# arduino_barebone.net
KiCad netlist of a schematic drawn in EAGLE
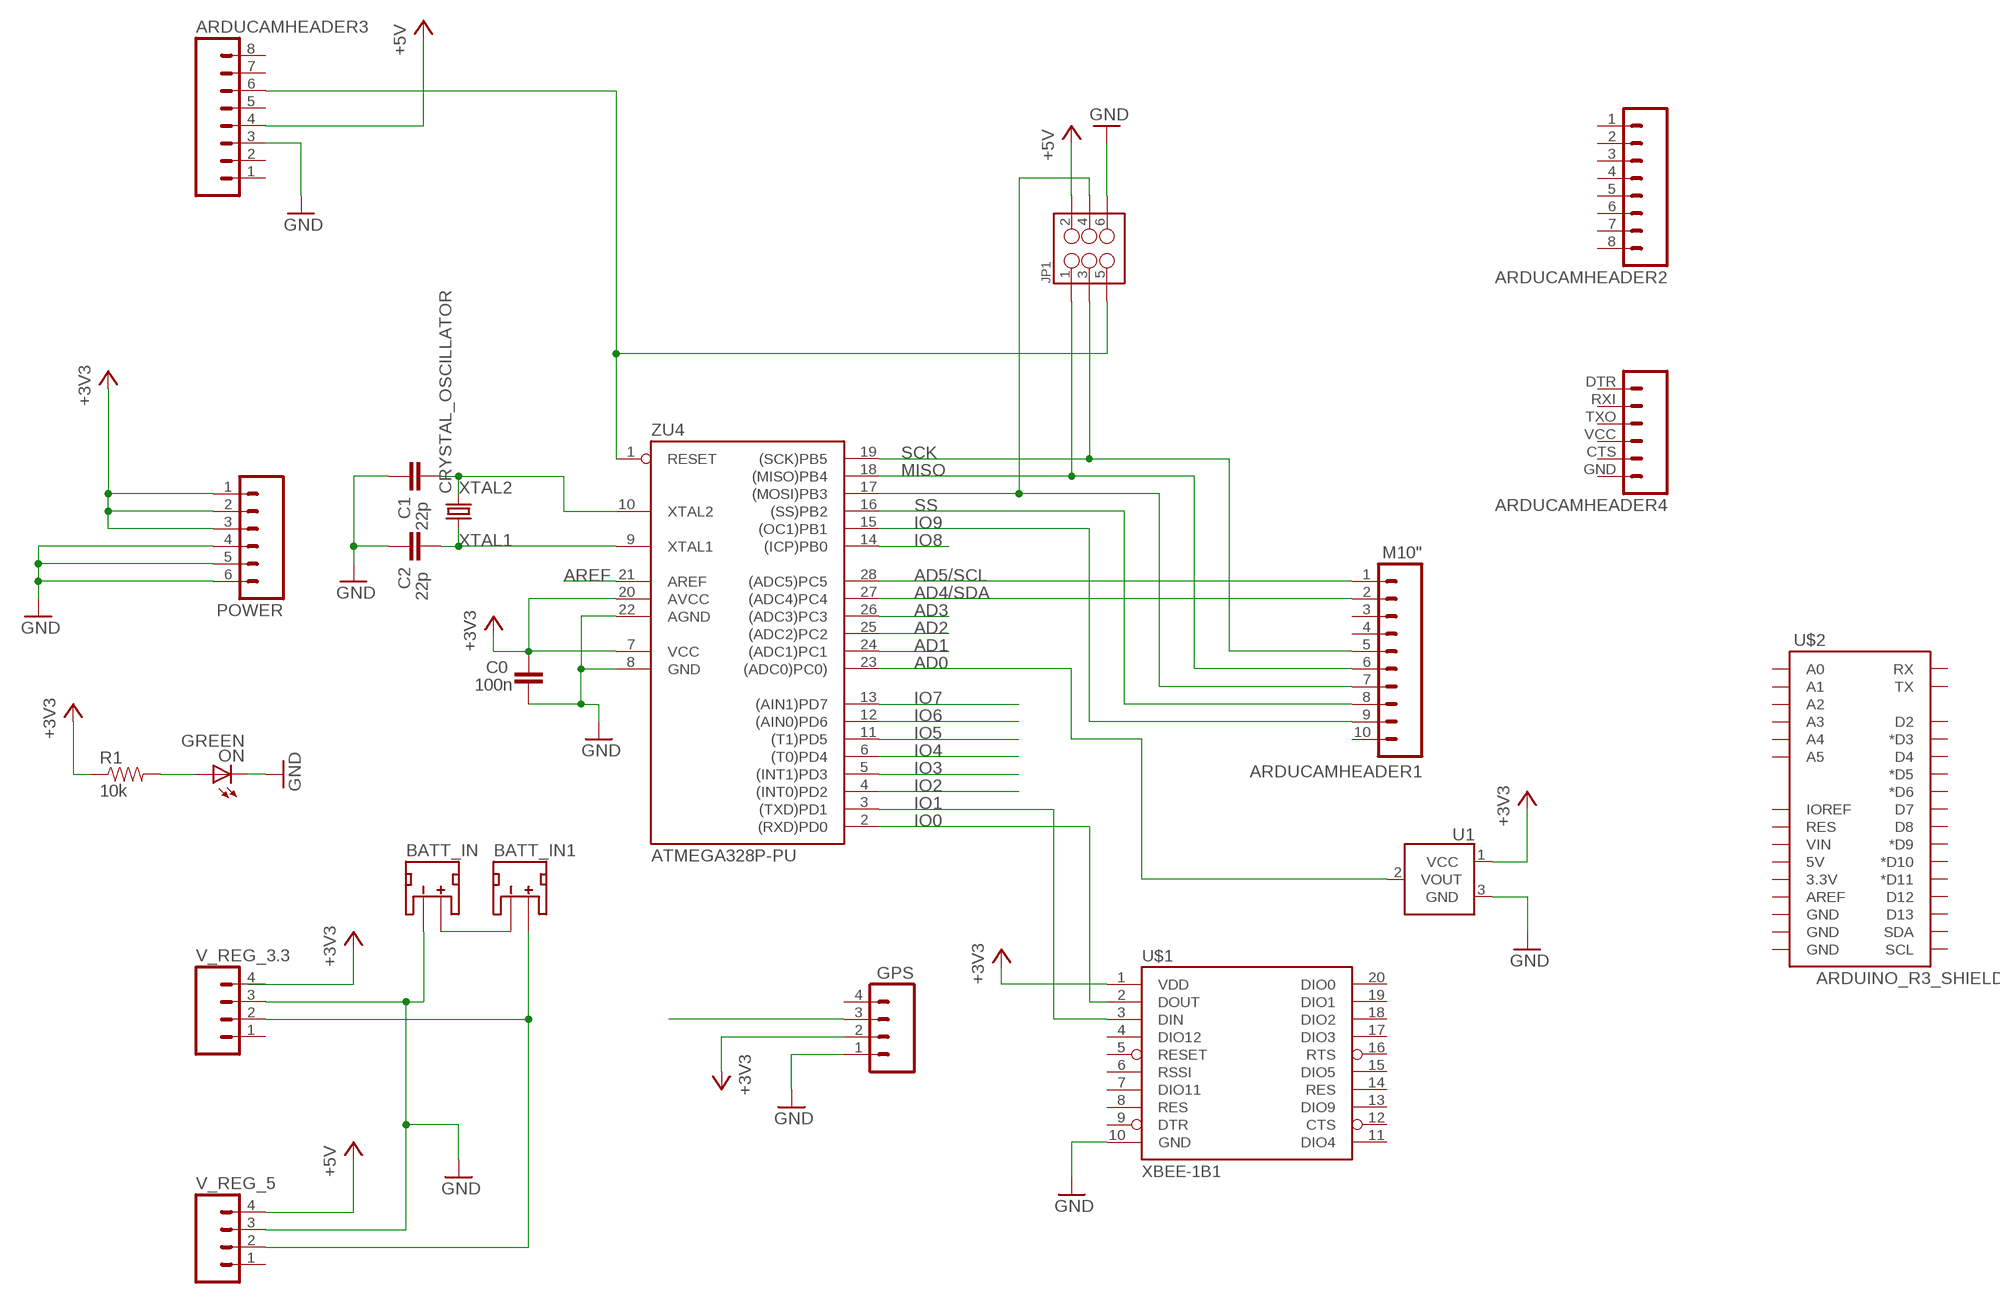
[diagram p0: schematic, sheet 1]

(export (version "E")
  (design (tool "Eeschema 10.0.6"))
  (components
    (comp (ref "ARDUCAMHEADER1")
      (value "M10\"")
      (footprint "eagle-import:1X10")
      (libsource (lib "eagle-import") (part "M10{dblquote}"))
    )
    (comp (ref "ARDUCAMHEADER2")
      (value "M081X08")
      (footprint "eagle-import:1X08")
      (libsource (lib "eagle-import") (part "M081X08"))
    )
    (comp (ref "ARDUCAMHEADER3")
      (value "M081X08")
      (footprint "eagle-import:1X08")
      (libsource (lib "eagle-import") (part "M081X08"))
    )
    (comp (ref "ARDUCAMHEADER4")
      (value "M06SIP")
      (footprint "eagle-import:1X06")
      (libsource (lib "eagle-import") (part "M06SIP"))
    )
    (comp (ref "BATT_IN")
      (value "JST_2MM_MALE")
      (footprint "eagle-import:JST-2-SMD")
      (libsource (lib "eagle-import") (part "JST_2MM_MALE"))
    )
    (comp (ref "BATT_IN1")
      (value "JST_2MM_MALE")
      (footprint "eagle-import:JST-2-SMD")
      (libsource (lib "eagle-import") (part "JST_2MM_MALE"))
    )
    (comp (ref "C0")
      (value "100n")
      (footprint "eagle-import:C0603-ROUND")
      (libsource (lib "eagle-import") (part "C-EU0603-RND"))
    )
    (comp (ref "C1")
      (value "22p")
      (footprint "eagle-import:C0603-ROUND")
      (libsource (lib "eagle-import") (part "C-EU0603-RND"))
    )
    (comp (ref "C2")
      (value "22p")
      (footprint "eagle-import:C0603-ROUND")
      (libsource (lib "eagle-import") (part "C-EU0603-RND"))
    )
    (comp (ref "CRYSTAL_OSCILLATOR")
      (value "CRYSTALHC49US")
      (footprint "eagle-import:HC49US")
      (libsource (lib "eagle-import") (part "CRYSTALHC49US"))
    )
    (comp (ref "GPS")
      (value "M04PTH")
      (footprint "eagle-import:1X04")
      (libsource (lib "eagle-import") (part "M04PTH"))
    )
    (comp (ref "JP1")
      (value "M03X2POGO_PINS")
      (footprint "eagle-import:2X3_POGO")
      (libsource (lib "eagle-import") (part "M03X2POGO_PINS"))
    )
    (comp (ref "ON")
      (value "GREEN")
      (footprint "eagle-import:CHIP-LED0805")
      (libsource (lib "eagle-import") (part "LEDCHIP-LED0805"))
    )
    (comp (ref "POWER")
      (value "M06LONGPADS")
      (footprint "eagle-import:1X06_LONGPADS")
      (libsource (lib "eagle-import") (part "M06LONGPADS"))
    )
    (comp (ref "R1")
      (value "10k")
      (footprint "eagle-import:0805")
      (libsource (lib "eagle-import") (part "RESISTOR"))
    )
    (comp (ref "U$1")
      (value "XBEE-1B1")
      (footprint "eagle-import:XBEE-1")
      (libsource (lib "eagle-import") (part "XBEE-1B1"))
    )
    (comp (ref "U$2")
      (value "ARDUINO_R3_SHIELD")
      (footprint "eagle-import:UNO_R3_SHIELD")
      (libsource (lib "eagle-import") (part "ARDUINO_R3_SHIELD"))
    )
    (comp (ref "U1")
      (value "TMP36GT9")
      (footprint "eagle-import:TO-92")
      (libsource (lib "eagle-import") (part "TMP36GT9"))
    )
    (comp (ref "V_REG_3.3")
      (value "M04PTH")
      (footprint "eagle-import:1X04")
      (libsource (lib "eagle-import") (part "M04PTH"))
    )
    (comp (ref "V_REG_5")
      (value "M04PTH")
      (footprint "eagle-import:1X04")
      (libsource (lib "eagle-import") (part "M04PTH"))
    )
    (comp (ref "ZU4")
      (value "ATMEGA328P-PU")
      (footprint "eagle-import:DIL28-3")
      (libsource (lib "eagle-import") (part "ATMEGA328P-PU"))
    )
  )
  (nets
    (net (code "1") (name "+3V3") (class "Default")
      (node (ref "C0") (pin "2") (pinfunction "2_2") (pintype "passive"))
      (node (ref "GPS") (pin "2") (pinfunction "2_2") (pintype "passive"))
      (node (ref "POWER") (pin "1") (pinfunction "1_1") (pintype "passive"))
      (node (ref "POWER") (pin "2") (pinfunction "2_2") (pintype "passive"))
      (node (ref "POWER") (pin "3") (pinfunction "3_3") (pintype "passive"))
      (node (ref "R1") (pin "1") (pinfunction "1_1") (pintype "passive"))
      (node (ref "U$1") (pin "1") (pinfunction "VDD_1") (pintype "power_in"))
      (node (ref "U1") (pin "1") (pinfunction "VCC_1") (pintype "bidirectional"))
      (node (ref "V_REG_3.3") (pin "4") (pinfunction "4_4") (pintype "passive"))
      (node (ref "ZU4") (pin "20") (pinfunction "AVCC_20") (pintype "power_in"))
      (node (ref "ZU4") (pin "7") (pinfunction "VCC_7") (pintype "power_in"))
    )
    (net (code "2") (name "+5V") (class "Default")
      (node (ref "ARDUCAMHEADER3") (pin "4") (pinfunction "4_4") (pintype "passive"))
      (node (ref "JP1") (pin "P$2") (pinfunction "2_P$2") (pintype "bidirectional"))
      (node (ref "V_REG_5") (pin "4") (pinfunction "4_4") (pintype "passive"))
    )
    (net (code "3") (name "/AD0") (class "Default")
      (node (ref "U1") (pin "2") (pinfunction "VOUT_2") (pintype "bidirectional"))
      (node (ref "ZU4") (pin "23") (pinfunction "(ADC0)PC0)_23") (pintype "bidirectional"))
    )
    (net (code "4") (name "/AD1") (class "Default")
      (node (ref "ZU4") (pin "24") (pinfunction "(ADC1)PC1_24") (pintype "bidirectional"))
    )
    (net (code "5") (name "/AD2") (class "Default")
      (node (ref "ZU4") (pin "25") (pinfunction "(ADC2)PC2_25") (pintype "bidirectional"))
    )
    (net (code "6") (name "/AD3") (class "Default")
      (node (ref "ZU4") (pin "26") (pinfunction "(ADC3)PC3_26") (pintype "bidirectional"))
    )
    (net (code "7") (name "/AD4{slash}SDA") (class "Default")
      (node (ref "ARDUCAMHEADER1") (pin "2") (pinfunction "2_2") (pintype "passive"))
      (node (ref "ZU4") (pin "27") (pinfunction "(ADC4)PC4_27") (pintype "bidirectional"))
    )
    (net (code "8") (name "/AD5{slash}SCL") (class "Default")
      (node (ref "ARDUCAMHEADER1") (pin "1") (pinfunction "1_1") (pintype "passive"))
      (node (ref "ZU4") (pin "28") (pinfunction "(ADC5)PC5_28") (pintype "bidirectional"))
    )
    (net (code "9") (name "/AREF") (class "Default")
      (node (ref "ZU4") (pin "21") (pinfunction "AREF_21") (pintype "passive"))
    )
    (net (code "10") (name "/IO0") (class "Default")
      (node (ref "U$1") (pin "2") (pinfunction "DOUT_2") (pintype "output"))
      (node (ref "ZU4") (pin "2") (pinfunction "(RXD)PD0_2") (pintype "bidirectional"))
    )
    (net (code "11") (name "/IO1") (class "Default")
      (node (ref "U$1") (pin "3") (pinfunction "DIN_3") (pintype "input"))
      (node (ref "ZU4") (pin "3") (pinfunction "(TXD)PD1_3") (pintype "bidirectional"))
    )
    (net (code "12") (name "/IO2") (class "Default")
      (node (ref "ZU4") (pin "4") (pinfunction "(INT0)PD2_4") (pintype "bidirectional"))
    )
    (net (code "13") (name "/IO3") (class "Default")
      (node (ref "ZU4") (pin "5") (pinfunction "(INT1)PD3_5") (pintype "bidirectional"))
    )
    (net (code "14") (name "/IO4") (class "Default")
      (node (ref "ZU4") (pin "6") (pinfunction "(T0)PD4_6") (pintype "bidirectional"))
    )
    (net (code "15") (name "/IO5") (class "Default")
      (node (ref "ZU4") (pin "11") (pinfunction "(T1)PD5_11") (pintype "bidirectional"))
    )
    (net (code "16") (name "/IO6") (class "Default")
      (node (ref "ZU4") (pin "12") (pinfunction "(AIN0)PD6_12") (pintype "bidirectional"))
    )
    (net (code "17") (name "/IO7") (class "Default")
      (node (ref "ZU4") (pin "13") (pinfunction "(AIN1)PD7_13") (pintype "bidirectional"))
    )
    (net (code "18") (name "/IO8") (class "Default")
      (node (ref "ZU4") (pin "14") (pinfunction "(ICP)PB0_14") (pintype "bidirectional"))
    )
    (net (code "19") (name "/IO9") (class "Default")
      (node (ref "ARDUCAMHEADER1") (pin "9") (pinfunction "9_9") (pintype "passive"))
      (node (ref "ZU4") (pin "15") (pinfunction "(OC1)PB1_15") (pintype "bidirectional"))
    )
    (net (code "20") (name "/MISO") (class "Default")
      (node (ref "ARDUCAMHEADER1") (pin "6") (pinfunction "6_6") (pintype "passive"))
      (node (ref "JP1") (pin "P$1") (pinfunction "1_P$1") (pintype "bidirectional"))
      (node (ref "ZU4") (pin "18") (pinfunction "(MISO)PB4_18") (pintype "bidirectional"))
    )
    (net (code "21") (name "/SCK") (class "Default")
      (node (ref "ARDUCAMHEADER1") (pin "5") (pinfunction "5_5") (pintype "passive"))
      (node (ref "JP1") (pin "P$3") (pinfunction "3_P$3") (pintype "bidirectional"))
      (node (ref "ZU4") (pin "19") (pinfunction "(SCK)PB5_19") (pintype "bidirectional"))
    )
    (net (code "22") (name "/SS") (class "Default")
      (node (ref "ARDUCAMHEADER1") (pin "8") (pinfunction "8_8") (pintype "passive"))
      (node (ref "ZU4") (pin "16") (pinfunction "(SS)PB2_16") (pintype "bidirectional"))
    )
    (net (code "23") (name "/XTAL1") (class "Default")
      (node (ref "C2") (pin "1") (pinfunction "1_1") (pintype "passive"))
      (node (ref "CRYSTAL_OSCILLATOR") (pin "1") (pinfunction "1_1") (pintype "passive"))
      (node (ref "ZU4") (pin "9") (pinfunction "XTAL1_9") (pintype "bidirectional"))
    )
    (net (code "24") (name "/XTAL2") (class "Default")
      (node (ref "C1") (pin "1") (pinfunction "1_1") (pintype "passive"))
      (node (ref "CRYSTAL_OSCILLATOR") (pin "2") (pinfunction "2_2") (pintype "passive"))
      (node (ref "ZU4") (pin "10") (pinfunction "XTAL2_10") (pintype "bidirectional"))
    )
    (net (code "25") (name "GND") (class "Default")
      (node (ref "ARDUCAMHEADER3") (pin "3") (pinfunction "3_3") (pintype "passive"))
      (node (ref "BATT_IN") (pin "1") (pinfunction "-_1") (pintype "bidirectional"))
      (node (ref "C0") (pin "1") (pinfunction "1_1") (pintype "passive"))
      (node (ref "C1") (pin "2") (pinfunction "2_2") (pintype "passive"))
      (node (ref "C2") (pin "2") (pinfunction "2_2") (pintype "passive"))
      (node (ref "GPS") (pin "1") (pinfunction "1_1") (pintype "passive"))
      (node (ref "JP1") (pin "P$6") (pinfunction "6_P$6") (pintype "bidirectional"))
      (node (ref "ON") (pin "C") (pinfunction "C_C") (pintype "passive"))
      (node (ref "POWER") (pin "4") (pinfunction "4_4") (pintype "passive"))
      (node (ref "POWER") (pin "5") (pinfunction "5_5") (pintype "passive"))
      (node (ref "POWER") (pin "6") (pinfunction "6_6") (pintype "passive"))
      (node (ref "U$1") (pin "10") (pinfunction "GND_10") (pintype "power_in"))
      (node (ref "U1") (pin "3") (pinfunction "GND_3") (pintype "bidirectional"))
      (node (ref "V_REG_3.3") (pin "3") (pinfunction "3_3") (pintype "passive"))
      (node (ref "V_REG_5") (pin "3") (pinfunction "3_3") (pintype "passive"))
      (node (ref "ZU4") (pin "22") (pinfunction "AGND_22") (pintype "power_in"))
      (node (ref "ZU4") (pin "8") (pinfunction "GND_8") (pintype "power_in"))
    )
    (net (code "26") (name "Net-(BATT_IN-+)") (class "Default")
      (node (ref "BATT_IN") (pin "2") (pinfunction "+_2") (pintype "bidirectional"))
      (node (ref "BATT_IN1") (pin "1") (pinfunction "-_1") (pintype "bidirectional"))
    )
    (net (code "27") (name "Net-(BATT_IN1-+)") (class "Default")
      (node (ref "BATT_IN1") (pin "2") (pinfunction "+_2") (pintype "bidirectional"))
      (node (ref "V_REG_3.3") (pin "2") (pinfunction "2_2") (pintype "passive"))
      (node (ref "V_REG_5") (pin "2") (pinfunction "2_2") (pintype "passive"))
    )
    (net (code "28") (name "Net-(JP1-4)") (class "Default")
      (node (ref "ARDUCAMHEADER1") (pin "7") (pinfunction "7_7") (pintype "passive"))
      (node (ref "JP1") (pin "P$4") (pinfunction "4_P$4") (pintype "bidirectional"))
      (node (ref "ZU4") (pin "17") (pinfunction "(MOSI)PB3_17") (pintype "bidirectional"))
    )
    (net (code "29") (name "Net-(JP1-5)") (class "Default")
      (node (ref "ARDUCAMHEADER3") (pin "6") (pinfunction "6_6") (pintype "passive"))
      (node (ref "JP1") (pin "P$5") (pinfunction "5_P$5") (pintype "bidirectional"))
      (node (ref "ZU4") (pin "1") (pinfunction "RESET_1") (pintype "input"))
    )
    (net (code "30") (name "Net-(ON-PadA)") (class "Default")
      (node (ref "ON") (pin "A") (pinfunction "A_A") (pintype "passive"))
      (node (ref "R1") (pin "2") (pinfunction "2_2") (pintype "passive"))
    )
    (net (code "31") (name "unconnected-(ARDUCAMHEADER1-Pad3)") (class "Default")
      (node (ref "ARDUCAMHEADER1") (pin "3") (pinfunction "3_3") (pintype "passive"))
    )
    (net (code "32") (name "unconnected-(ARDUCAMHEADER1-Pad4)") (class "Default")
      (node (ref "ARDUCAMHEADER1") (pin "4") (pinfunction "4_4") (pintype "passive"))
    )
    (net (code "33") (name "unconnected-(ARDUCAMHEADER1-Pad10)") (class "Default")
      (node (ref "ARDUCAMHEADER1") (pin "10") (pinfunction "10_10") (pintype "passive"))
    )
    (net (code "34") (name "unconnected-(ARDUCAMHEADER2-Pad1)") (class "Default")
      (node (ref "ARDUCAMHEADER2") (pin "1") (pinfunction "1_1") (pintype "passive"))
    )
    (net (code "35") (name "unconnected-(ARDUCAMHEADER2-Pad2)") (class "Default")
      (node (ref "ARDUCAMHEADER2") (pin "2") (pinfunction "2_2") (pintype "passive"))
    )
    (net (code "36") (name "unconnected-(ARDUCAMHEADER2-Pad3)") (class "Default")
      (node (ref "ARDUCAMHEADER2") (pin "3") (pinfunction "3_3") (pintype "passive"))
    )
    (net (code "37") (name "unconnected-(ARDUCAMHEADER2-Pad4)") (class "Default")
      (node (ref "ARDUCAMHEADER2") (pin "4") (pinfunction "4_4") (pintype "passive"))
    )
    (net (code "38") (name "unconnected-(ARDUCAMHEADER2-Pad5)") (class "Default")
      (node (ref "ARDUCAMHEADER2") (pin "5") (pinfunction "5_5") (pintype "passive"))
    )
    (net (code "39") (name "unconnected-(ARDUCAMHEADER2-Pad6)") (class "Default")
      (node (ref "ARDUCAMHEADER2") (pin "6") (pinfunction "6_6") (pintype "passive"))
    )
    (net (code "40") (name "unconnected-(ARDUCAMHEADER2-Pad7)") (class "Default")
      (node (ref "ARDUCAMHEADER2") (pin "7") (pinfunction "7_7") (pintype "passive"))
    )
    (net (code "41") (name "unconnected-(ARDUCAMHEADER2-Pad8)") (class "Default")
      (node (ref "ARDUCAMHEADER2") (pin "8") (pinfunction "8_8") (pintype "passive"))
    )
    (net (code "42") (name "unconnected-(ARDUCAMHEADER3-Pad1)") (class "Default")
      (node (ref "ARDUCAMHEADER3") (pin "1") (pinfunction "1_1") (pintype "passive"))
    )
    (net (code "43") (name "unconnected-(ARDUCAMHEADER3-Pad2)") (class "Default")
      (node (ref "ARDUCAMHEADER3") (pin "2") (pinfunction "2_2") (pintype "passive"))
    )
    (net (code "44") (name "unconnected-(ARDUCAMHEADER3-Pad5)") (class "Default")
      (node (ref "ARDUCAMHEADER3") (pin "5") (pinfunction "5_5") (pintype "passive"))
    )
    (net (code "45") (name "unconnected-(ARDUCAMHEADER3-Pad7)") (class "Default")
      (node (ref "ARDUCAMHEADER3") (pin "7") (pinfunction "7_7") (pintype "passive"))
    )
    (net (code "46") (name "unconnected-(ARDUCAMHEADER3-Pad8)") (class "Default")
      (node (ref "ARDUCAMHEADER3") (pin "8") (pinfunction "8_8") (pintype "passive"))
    )
    (net (code "47") (name "unconnected-(ARDUCAMHEADER4-1-PadDTR)") (class "Default")
      (node (ref "ARDUCAMHEADER4") (pin "DTR") (pinfunction "1_DTR") (pintype "passive"))
    )
    (net (code "48") (name "unconnected-(ARDUCAMHEADER4-2-PadRXI)") (class "Default")
      (node (ref "ARDUCAMHEADER4") (pin "RXI") (pinfunction "2_RXI") (pintype "passive"))
    )
    (net (code "49") (name "unconnected-(ARDUCAMHEADER4-3-PadTXO)") (class "Default")
      (node (ref "ARDUCAMHEADER4") (pin "TXO") (pinfunction "3_TXO") (pintype "passive"))
    )
    (net (code "50") (name "unconnected-(ARDUCAMHEADER4-4-PadVCC)") (class "Default")
      (node (ref "ARDUCAMHEADER4") (pin "VCC") (pinfunction "4_VCC") (pintype "passive"))
    )
    (net (code "51") (name "unconnected-(ARDUCAMHEADER4-5-PadCTS)") (class "Default")
      (node (ref "ARDUCAMHEADER4") (pin "CTS") (pinfunction "5_CTS") (pintype "passive"))
    )
    (net (code "52") (name "unconnected-(ARDUCAMHEADER4-6-PadGND)") (class "Default")
      (node (ref "ARDUCAMHEADER4") (pin "GND") (pinfunction "6_GND") (pintype "passive"))
    )
    (net (code "53") (name "unconnected-(BATT_IN-PAD1-PadNC1)") (class "Default")
      (node (ref "BATT_IN") (pin "NC1") (pinfunction "PAD1_NC1") (pintype "bidirectional"))
    )
    (net (code "54") (name "unconnected-(BATT_IN-PAD2-PadNC2)") (class "Default")
      (node (ref "BATT_IN") (pin "NC2") (pinfunction "PAD2_NC2") (pintype "bidirectional"))
    )
    (net (code "55") (name "unconnected-(BATT_IN1-PAD1-PadNC1)") (class "Default")
      (node (ref "BATT_IN1") (pin "NC1") (pinfunction "PAD1_NC1") (pintype "bidirectional"))
    )
    (net (code "56") (name "unconnected-(BATT_IN1-PAD2-PadNC2)") (class "Default")
      (node (ref "BATT_IN1") (pin "NC2") (pinfunction "PAD2_NC2") (pintype "bidirectional"))
    )
    (net (code "57") (name "unconnected-(GPS-Pad3)") (class "Default")
      (node (ref "GPS") (pin "3") (pinfunction "3_3") (pintype "passive"))
    )
    (net (code "58") (name "unconnected-(GPS-Pad4)") (class "Default")
      (node (ref "GPS") (pin "4") (pinfunction "4_4") (pintype "passive"))
    )
    (net (code "59") (name "unconnected-(U$1-CTS-Pad12)") (class "Default")
      (node (ref "U$1") (pin "12") (pinfunction "CTS_12") (pintype "output"))
    )
    (net (code "60") (name "unconnected-(U$1-DIO0-Pad20)") (class "Default")
      (node (ref "U$1") (pin "20") (pinfunction "DIO0_20") (pintype "bidirectional"))
    )
    (net (code "61") (name "unconnected-(U$1-DIO1-Pad19)") (class "Default")
      (node (ref "U$1") (pin "19") (pinfunction "DIO1_19") (pintype "bidirectional"))
    )
    (net (code "62") (name "unconnected-(U$1-DIO2-Pad18)") (class "Default")
      (node (ref "U$1") (pin "18") (pinfunction "DIO2_18") (pintype "bidirectional"))
    )
    (net (code "63") (name "unconnected-(U$1-DIO3-Pad17)") (class "Default")
      (node (ref "U$1") (pin "17") (pinfunction "DIO3_17") (pintype "bidirectional"))
    )
    (net (code "64") (name "unconnected-(U$1-DIO4-Pad11)") (class "Default")
      (node (ref "U$1") (pin "11") (pinfunction "DIO4_11") (pintype "bidirectional"))
    )
    (net (code "65") (name "unconnected-(U$1-DIO5-Pad15)") (class "Default")
      (node (ref "U$1") (pin "15") (pinfunction "DIO5_15") (pintype "bidirectional"))
    )
    (net (code "66") (name "unconnected-(U$1-DIO9-Pad13)") (class "Default")
      (node (ref "U$1") (pin "13") (pinfunction "DIO9_13") (pintype "bidirectional"))
    )
    (net (code "67") (name "unconnected-(U$1-DIO11-Pad7)") (class "Default")
      (node (ref "U$1") (pin "7") (pinfunction "DIO11_7") (pintype "bidirectional"))
    )
    (net (code "68") (name "unconnected-(U$1-DIO12-Pad4)") (class "Default")
      (node (ref "U$1") (pin "4") (pinfunction "DIO12_4") (pintype "bidirectional"))
    )
    (net (code "69") (name "unconnected-(U$1-DTR-Pad9)") (class "Default")
      (node (ref "U$1") (pin "9") (pinfunction "DTR_9") (pintype "bidirectional"))
    )
    (net (code "70") (name "unconnected-(U$1-RES-Pad8)") (class "Default")
      (node (ref "U$1") (pin "8") (pinfunction "RES_8") (pintype "bidirectional"))
    )
    (net (code "71") (name "unconnected-(U$1-RES-Pad14)") (class "Default")
      (node (ref "U$1") (pin "14") (pinfunction "RES_14") (pintype "bidirectional"))
    )
    (net (code "72") (name "unconnected-(U$1-RESET-Pad5)") (class "Default")
      (node (ref "U$1") (pin "5") (pinfunction "RESET_5") (pintype "input"))
    )
    (net (code "73") (name "unconnected-(U$1-RSSI-Pad6)") (class "Default")
      (node (ref "U$1") (pin "6") (pinfunction "RSSI_6") (pintype "bidirectional"))
    )
    (net (code "74") (name "unconnected-(U$1-RTS-Pad16)") (class "Default")
      (node (ref "U$1") (pin "16") (pinfunction "RTS_16") (pintype "input"))
    )
    (net (code "75") (name "unconnected-(U$2-*D3-PadD3)") (class "Default")
      (node (ref "U$2") (pin "D3") (pinfunction "*D3_D3") (pintype "bidirectional"))
    )
    (net (code "76") (name "unconnected-(U$2-*D5-PadD5)") (class "Default")
      (node (ref "U$2") (pin "D5") (pinfunction "*D5_D5") (pintype "bidirectional"))
    )
    (net (code "77") (name "unconnected-(U$2-*D6-PadD6)") (class "Default")
      (node (ref "U$2") (pin "D6") (pinfunction "*D6_D6") (pintype "bidirectional"))
    )
    (net (code "78") (name "unconnected-(U$2-*D9-PadD9)") (class "Default")
      (node (ref "U$2") (pin "D9") (pinfunction "*D9_D9") (pintype "bidirectional"))
    )
    (net (code "79") (name "unconnected-(U$2-*D10-PadD10)") (class "Default")
      (node (ref "U$2") (pin "D10") (pinfunction "*D10_D10") (pintype "bidirectional"))
    )
    (net (code "80") (name "unconnected-(U$2-*D11-PadD11)") (class "Default")
      (node (ref "U$2") (pin "D11") (pinfunction "*D11_D11") (pintype "bidirectional"))
    )
    (net (code "81") (name "unconnected-(U$2-GND-PadGND@0)") (class "Default")
      (node (ref "U$2") (pin "GND@0") (pinfunction "GND_GND@0") (pintype "bidirectional"))
    )
    (net (code "82") (name "unconnected-(U$2-GND-PadGND@1)") (class "Default")
      (node (ref "U$2") (pin "GND@1") (pinfunction "GND_GND@1") (pintype "bidirectional"))
    )
    (net (code "83") (name "unconnected-(U$2-GND-PadGND@2)") (class "Default")
      (node (ref "U$2") (pin "GND@2") (pinfunction "GND_GND@2") (pintype "bidirectional"))
    )
    (net (code "84") (name "unconnected-(U$2-Pad3.3V)") (class "Default")
      (node (ref "U$2") (pin "3.3V") (pinfunction "3.3V_3.3V") (pintype "bidirectional"))
    )
    (net (code "85") (name "unconnected-(U$2-Pad5V)") (class "Default")
      (node (ref "U$2") (pin "5V") (pinfunction "5V_5V") (pintype "bidirectional"))
    )
    (net (code "86") (name "unconnected-(U$2-PadA0)") (class "Default")
      (node (ref "U$2") (pin "A0") (pinfunction "A0_A0") (pintype "bidirectional"))
    )
    (net (code "87") (name "unconnected-(U$2-PadA1)") (class "Default")
      (node (ref "U$2") (pin "A1") (pinfunction "A1_A1") (pintype "bidirectional"))
    )
    (net (code "88") (name "unconnected-(U$2-PadA2)") (class "Default")
      (node (ref "U$2") (pin "A2") (pinfunction "A2_A2") (pintype "bidirectional"))
    )
    (net (code "89") (name "unconnected-(U$2-PadA3)") (class "Default")
      (node (ref "U$2") (pin "A3") (pinfunction "A3_A3") (pintype "bidirectional"))
    )
    (net (code "90") (name "unconnected-(U$2-PadA4)") (class "Default")
      (node (ref "U$2") (pin "A4") (pinfunction "A4_A4") (pintype "bidirectional"))
    )
    (net (code "91") (name "unconnected-(U$2-PadA5)") (class "Default")
      (node (ref "U$2") (pin "A5") (pinfunction "A5_A5") (pintype "bidirectional"))
    )
    (net (code "92") (name "unconnected-(U$2-PadAREF)") (class "Default")
      (node (ref "U$2") (pin "AREF") (pinfunction "AREF_AREF") (pintype "bidirectional"))
    )
    (net (code "93") (name "unconnected-(U$2-PadD2)") (class "Default")
      (node (ref "U$2") (pin "D2") (pinfunction "D2_D2") (pintype "bidirectional"))
    )
    (net (code "94") (name "unconnected-(U$2-PadD4)") (class "Default")
      (node (ref "U$2") (pin "D4") (pinfunction "D4_D4") (pintype "bidirectional"))
    )
    (net (code "95") (name "unconnected-(U$2-PadD7)") (class "Default")
      (node (ref "U$2") (pin "D7") (pinfunction "D7_D7") (pintype "bidirectional"))
    )
    (net (code "96") (name "unconnected-(U$2-PadD8)") (class "Default")
      (node (ref "U$2") (pin "D8") (pinfunction "D8_D8") (pintype "bidirectional"))
    )
    (net (code "97") (name "unconnected-(U$2-PadD12)") (class "Default")
      (node (ref "U$2") (pin "D12") (pinfunction "D12_D12") (pintype "bidirectional"))
    )
    (net (code "98") (name "unconnected-(U$2-PadD13)") (class "Default")
      (node (ref "U$2") (pin "D13") (pinfunction "D13_D13") (pintype "bidirectional"))
    )
    (net (code "99") (name "unconnected-(U$2-PadIOREF)") (class "Default")
      (node (ref "U$2") (pin "IOREF") (pinfunction "IOREF_IOREF") (pintype "bidirectional"))
    )
    (net (code "100") (name "unconnected-(U$2-PadRES)") (class "Default")
      (node (ref "U$2") (pin "RES") (pinfunction "RES_RES") (pintype "bidirectional"))
    )
    (net (code "101") (name "unconnected-(U$2-PadRX)") (class "Default")
      (node (ref "U$2") (pin "RX") (pinfunction "RX_RX") (pintype "bidirectional"))
    )
    (net (code "102") (name "unconnected-(U$2-PadSCL)") (class "Default")
      (node (ref "U$2") (pin "SCL") (pinfunction "SCL_SCL") (pintype "bidirectional"))
    )
    (net (code "103") (name "unconnected-(U$2-PadSDA)") (class "Default")
      (node (ref "U$2") (pin "SDA") (pinfunction "SDA_SDA") (pintype "bidirectional"))
    )
    (net (code "104") (name "unconnected-(U$2-PadTX)") (class "Default")
      (node (ref "U$2") (pin "TX") (pinfunction "TX_TX") (pintype "bidirectional"))
    )
    (net (code "105") (name "unconnected-(U$2-PadVIN)") (class "Default")
      (node (ref "U$2") (pin "VIN") (pinfunction "VIN_VIN") (pintype "bidirectional"))
    )
    (net (code "106") (name "unconnected-(V_REG_3.3-Pad1)") (class "Default")
      (node (ref "V_REG_3.3") (pin "1") (pinfunction "1_1") (pintype "passive"))
    )
    (net (code "107") (name "unconnected-(V_REG_5-Pad1)") (class "Default")
      (node (ref "V_REG_5") (pin "1") (pinfunction "1_1") (pintype "passive"))
    )
  )
)
